# ES_PRJ_6C_2L_2026.net
KiCad netlist of a schematic drawn in Altium Designer
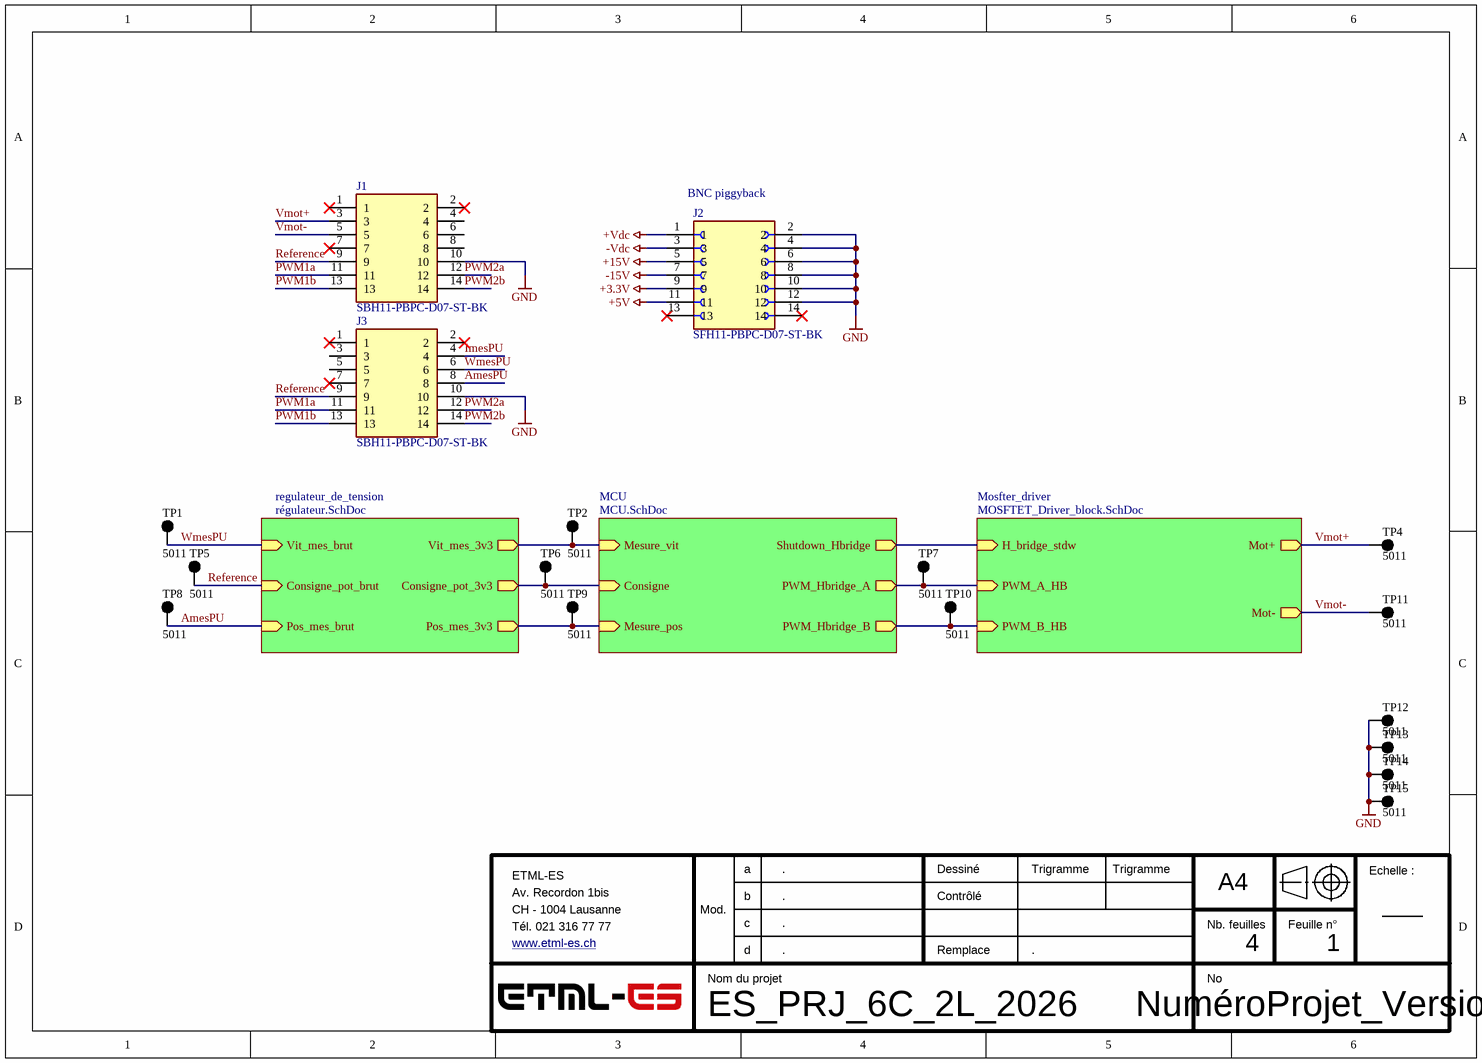
[diagram p0: ES_PRJ_6C_2L_2026.SchDoc]

(export (version "E")
  (design (tool "Eeschema 10.0.6"))
  (components
    (comp (ref "J1")
      (value "SBH11-PBPC-D07-ST-BK")
      (footprint "SULLINS_SBH11-PBPC-D07-ST-BK")
      (description "Connector Header Through Hole 14 position 0.100 (2.54mm)")
      (fields (field (name "MF") "Sullins Connector"))
      (libsource (lib "SBH11-PBPC-D07-ST-BK") (part "SBH11-PBPC-D07-ST-BK"))
    )
    (comp (ref "J2")
      (value "SFH11-PBPC-D07-ST-BK")
      (footprint "SULLINS_SFH11-PBPC-D07-ST-BK")
      (description "14 Position Header Connector Through Hole")
      (fields (field (name "MF") "Sullins Connector"))
      (libsource (lib "SFH11-PBPC-D07-ST-BK") (part "SFH11-PBPC-D07-ST-BK"))
    )
    (comp (ref "J3")
      (value "SBH11-PBPC-D07-ST-BK")
      (footprint "SULLINS_SBH11-PBPC-D07-ST-BK")
      (description "Connector Header Through Hole 14 position 0.100 (2.54mm)")
      (fields (field (name "MF") "Sullins Connector"))
      (libsource (lib "SBH11-PBPC-D07-ST-BK") (part "SBH11-PBPC-D07-ST-BK"))
    )
    (comp (ref "TP1")
      (value "5011")
      (footprint "KSTN-5011_V")
      (description "Test Point, Black, Through Hole, RoHS, Bulk")
      (fields (field (name "MANUFACTURER") "Keystone"))
      (libsource (lib "Altium Content Vault") (part "TESTPOINT_BLACK"))
    )
    (comp (ref "TP2")
      (value "5011")
      (footprint "KSTN-5011_V")
      (description "Test Point, Black, Through Hole, RoHS, Bulk")
      (fields (field (name "MANUFACTURER") "Keystone"))
      (libsource (lib "Altium Content Vault") (part "TESTPOINT_BLACK"))
    )
    (comp (ref "TP4")
      (value "5011")
      (footprint "KSTN-5011_V")
      (description "Test Point, Black, Through Hole, RoHS, Bulk")
      (fields (field (name "MANUFACTURER") "Keystone"))
      (libsource (lib "Altium Content Vault") (part "TESTPOINT_BLACK"))
    )
    (comp (ref "TP5")
      (value "5011")
      (footprint "KSTN-5011_V")
      (description "Test Point, Black, Through Hole, RoHS, Bulk")
      (fields (field (name "MANUFACTURER") "Keystone"))
      (libsource (lib "Altium Content Vault") (part "TESTPOINT_BLACK"))
    )
    (comp (ref "TP6")
      (value "5011")
      (footprint "KSTN-5011_V")
      (description "Test Point, Black, Through Hole, RoHS, Bulk")
      (fields (field (name "MANUFACTURER") "Keystone"))
      (libsource (lib "Altium Content Vault") (part "TESTPOINT_BLACK"))
    )
    (comp (ref "TP7")
      (value "5011")
      (footprint "KSTN-5011_V")
      (description "Test Point, Black, Through Hole, RoHS, Bulk")
      (fields (field (name "MANUFACTURER") "Keystone"))
      (libsource (lib "Altium Content Vault") (part "TESTPOINT_BLACK"))
    )
    (comp (ref "TP8")
      (value "5011")
      (footprint "KSTN-5011_V")
      (description "Test Point, Black, Through Hole, RoHS, Bulk")
      (fields (field (name "MANUFACTURER") "Keystone"))
      (libsource (lib "Altium Content Vault") (part "TESTPOINT_BLACK"))
    )
    (comp (ref "TP9")
      (value "5011")
      (footprint "KSTN-5011_V")
      (description "Test Point, Black, Through Hole, RoHS, Bulk")
      (fields (field (name "MANUFACTURER") "Keystone"))
      (libsource (lib "Altium Content Vault") (part "TESTPOINT_BLACK"))
    )
    (comp (ref "TP10")
      (value "5011")
      (footprint "KSTN-5011_V")
      (description "Test Point, Black, Through Hole, RoHS, Bulk")
      (fields (field (name "MANUFACTURER") "Keystone"))
      (libsource (lib "Altium Content Vault") (part "TESTPOINT_BLACK"))
    )
    (comp (ref "TP11")
      (value "5011")
      (footprint "KSTN-5011_V")
      (description "Test Point, Black, Through Hole, RoHS, Bulk")
      (fields (field (name "MANUFACTURER") "Keystone"))
      (libsource (lib "Altium Content Vault") (part "TESTPOINT_BLACK"))
    )
    (comp (ref "TP12")
      (value "5011")
      (footprint "KSTN-5011_V")
      (description "Test Point, Black, Through Hole, RoHS, Bulk")
      (fields (field (name "MANUFACTURER") "Keystone"))
      (libsource (lib "Altium Content Vault") (part "TESTPOINT_BLACK"))
    )
    (comp (ref "TP13")
      (value "5011")
      (footprint "KSTN-5011_V")
      (description "Test Point, Black, Through Hole, RoHS, Bulk")
      (fields (field (name "MANUFACTURER") "Keystone"))
      (libsource (lib "Altium Content Vault") (part "TESTPOINT_BLACK"))
    )
    (comp (ref "TP14")
      (value "5011")
      (footprint "KSTN-5011_V")
      (description "Test Point, Black, Through Hole, RoHS, Bulk")
      (fields (field (name "MANUFACTURER") "Keystone"))
      (libsource (lib "Altium Content Vault") (part "TESTPOINT_BLACK"))
    )
    (comp (ref "TP15")
      (value "5011")
      (footprint "KSTN-5011_V")
      (description "Test Point, Black, Through Hole, RoHS, Bulk")
      (fields (field (name "MANUFACTURER") "Keystone"))
      (libsource (lib "Altium Content Vault") (part "TESTPOINT_BLACK"))
    )
  )
  (nets
    (net (code "1") (name "+3.3V") (class "Default")
      (node (ref "J2") (pin "9") (pinfunction "9_9") (pintype "passive"))
    )
    (net (code "2") (name "+5V") (class "Default")
      (node (ref "J2") (pin "11") (pinfunction "11_11") (pintype "passive"))
    )
    (net (code "3") (name "+15V") (class "Default")
      (node (ref "J2") (pin "5") (pinfunction "5_5") (pintype "passive"))
    )
    (net (code "4") (name "+Vdc") (class "Default")
      (node (ref "J2") (pin "1") (pinfunction "1_1") (pintype "passive"))
    )
    (net (code "5") (name "-15V") (class "Default")
      (node (ref "J2") (pin "7") (pinfunction "7_7") (pintype "passive"))
    )
    (net (code "6") (name "-Vdc") (class "Default")
      (node (ref "J2") (pin "3") (pinfunction "3_3") (pintype "passive"))
    )
    (net (code "7") (name "/AmesPU") (class "Default")
      (node (ref "J3") (pin "8") (pinfunction "8_8") (pintype "passive"))
      (node (ref "TP8") (pin "1") (pinfunction "1_1") (pintype "passive"))
    )
    (net (code "8") (name "/Consigne_pot_3v3") (class "Default")
      (node (ref "TP6") (pin "1") (pinfunction "1_1") (pintype "passive"))
    )
    (net (code "9") (name "/ImesPU") (class "Default")
      (node (ref "J3") (pin "4") (pinfunction "4_4") (pintype "passive"))
    )
    (net (code "10") (name "/PWM1a") (class "Default")
      (node (ref "J1") (pin "11") (pinfunction "11_11") (pintype "passive"))
      (node (ref "J3") (pin "11") (pinfunction "11_11") (pintype "passive"))
    )
    (net (code "11") (name "/PWM1b") (class "Default")
      (node (ref "J1") (pin "13") (pinfunction "13_13") (pintype "passive"))
      (node (ref "J3") (pin "13") (pinfunction "13_13") (pintype "passive"))
    )
    (net (code "12") (name "/PWM2a") (class "Default")
      (node (ref "J1") (pin "12") (pinfunction "12_12") (pintype "passive"))
      (node (ref "J3") (pin "12") (pinfunction "12_12") (pintype "passive"))
    )
    (net (code "13") (name "/PWM2b") (class "Default")
      (node (ref "J1") (pin "14") (pinfunction "14_14") (pintype "passive"))
      (node (ref "J3") (pin "14") (pinfunction "14_14") (pintype "passive"))
    )
    (net (code "14") (name "/PWM_Hbridge_A") (class "Default")
      (node (ref "TP7") (pin "1") (pinfunction "1_1") (pintype "passive"))
    )
    (net (code "15") (name "/PWM_Hbridge_B") (class "Default")
      (node (ref "TP10") (pin "1") (pinfunction "1_1") (pintype "passive"))
    )
    (net (code "16") (name "/Pos_mes_3v3") (class "Default")
      (node (ref "TP9") (pin "1") (pinfunction "1_1") (pintype "passive"))
    )
    (net (code "17") (name "/Reference") (class "Default")
      (node (ref "J1") (pin "9") (pinfunction "9_9") (pintype "passive"))
      (node (ref "J3") (pin "9") (pinfunction "9_9") (pintype "passive"))
      (node (ref "TP5") (pin "1") (pinfunction "1_1") (pintype "passive"))
    )
    (net (code "19") (name "/Vit_mes_3v3") (class "Default")
      (node (ref "TP2") (pin "1") (pinfunction "1_1") (pintype "passive"))
    )
    (net (code "20") (name "/Vmot+") (class "Default")
      (node (ref "J1") (pin "3") (pinfunction "3_3") (pintype "passive"))
      (node (ref "TP4") (pin "1") (pinfunction "1_1") (pintype "passive"))
    )
    (net (code "21") (name "/Vmot-") (class "Default")
      (node (ref "J1") (pin "5") (pinfunction "5_5") (pintype "passive"))
      (node (ref "TP11") (pin "1") (pinfunction "1_1") (pintype "passive"))
    )
    (net (code "22") (name "/WmesPU") (class "Default")
      (node (ref "J3") (pin "6") (pinfunction "6_6") (pintype "passive"))
      (node (ref "TP1") (pin "1") (pinfunction "1_1") (pintype "passive"))
    )
    (net (code "23") (name "GND") (class "Default")
      (node (ref "J1") (pin "10") (pinfunction "10_10") (pintype "passive"))
      (node (ref "J2") (pin "10") (pinfunction "10_10") (pintype "passive"))
      (node (ref "J2") (pin "12") (pinfunction "12_12") (pintype "passive"))
      (node (ref "J2") (pin "2") (pinfunction "2_2") (pintype "passive"))
      (node (ref "J2") (pin "4") (pinfunction "4_4") (pintype "passive"))
      (node (ref "J2") (pin "6") (pinfunction "6_6") (pintype "passive"))
      (node (ref "J2") (pin "8") (pinfunction "8_8") (pintype "passive"))
      (node (ref "J3") (pin "10") (pinfunction "10_10") (pintype "passive"))
      (node (ref "TP12") (pin "1") (pinfunction "1_1") (pintype "passive"))
      (node (ref "TP13") (pin "1") (pinfunction "1_1") (pintype "passive"))
      (node (ref "TP14") (pin "1") (pinfunction "1_1") (pintype "passive"))
      (node (ref "TP15") (pin "1") (pinfunction "1_1") (pintype "passive"))
    )
    (net (code "24") (name "unconnected-(J1-Pad1)") (class "Default")
      (node (ref "J1") (pin "1") (pinfunction "1_1") (pintype "passive+no_connect"))
    )
    (net (code "25") (name "unconnected-(J1-Pad2)") (class "Default")
      (node (ref "J1") (pin "2") (pinfunction "2_2") (pintype "passive+no_connect"))
    )
    (net (code "26") (name "unconnected-(J1-Pad4)") (class "Default")
      (node (ref "J1") (pin "4") (pinfunction "4_4") (pintype "passive"))
    )
    (net (code "27") (name "unconnected-(J1-Pad6)") (class "Default")
      (node (ref "J1") (pin "6") (pinfunction "6_6") (pintype "passive"))
    )
    (net (code "28") (name "unconnected-(J1-Pad7)") (class "Default")
      (node (ref "J1") (pin "7") (pinfunction "7_7") (pintype "passive+no_connect"))
    )
    (net (code "29") (name "unconnected-(J1-Pad8)") (class "Default")
      (node (ref "J1") (pin "8") (pinfunction "8_8") (pintype "passive"))
    )
    (net (code "30") (name "unconnected-(J2-Pad13)") (class "Default")
      (node (ref "J2") (pin "13") (pinfunction "13_13") (pintype "passive+no_connect"))
    )
    (net (code "31") (name "unconnected-(J2-Pad14)") (class "Default")
      (node (ref "J2") (pin "14") (pinfunction "14_14") (pintype "passive+no_connect"))
    )
    (net (code "32") (name "unconnected-(J3-Pad1)") (class "Default")
      (node (ref "J3") (pin "1") (pinfunction "1_1") (pintype "passive+no_connect"))
    )
    (net (code "33") (name "unconnected-(J3-Pad2)") (class "Default")
      (node (ref "J3") (pin "2") (pinfunction "2_2") (pintype "passive+no_connect"))
    )
    (net (code "34") (name "unconnected-(J3-Pad3)") (class "Default")
      (node (ref "J3") (pin "3") (pinfunction "3_3") (pintype "passive"))
    )
    (net (code "35") (name "unconnected-(J3-Pad5)") (class "Default")
      (node (ref "J3") (pin "5") (pinfunction "5_5") (pintype "passive"))
    )
    (net (code "36") (name "unconnected-(J3-Pad7)") (class "Default")
      (node (ref "J3") (pin "7") (pinfunction "7_7") (pintype "passive+no_connect"))
    )
  )
)
